# drive.net
KiCad netlist of a schematic drawn in Altium Designer
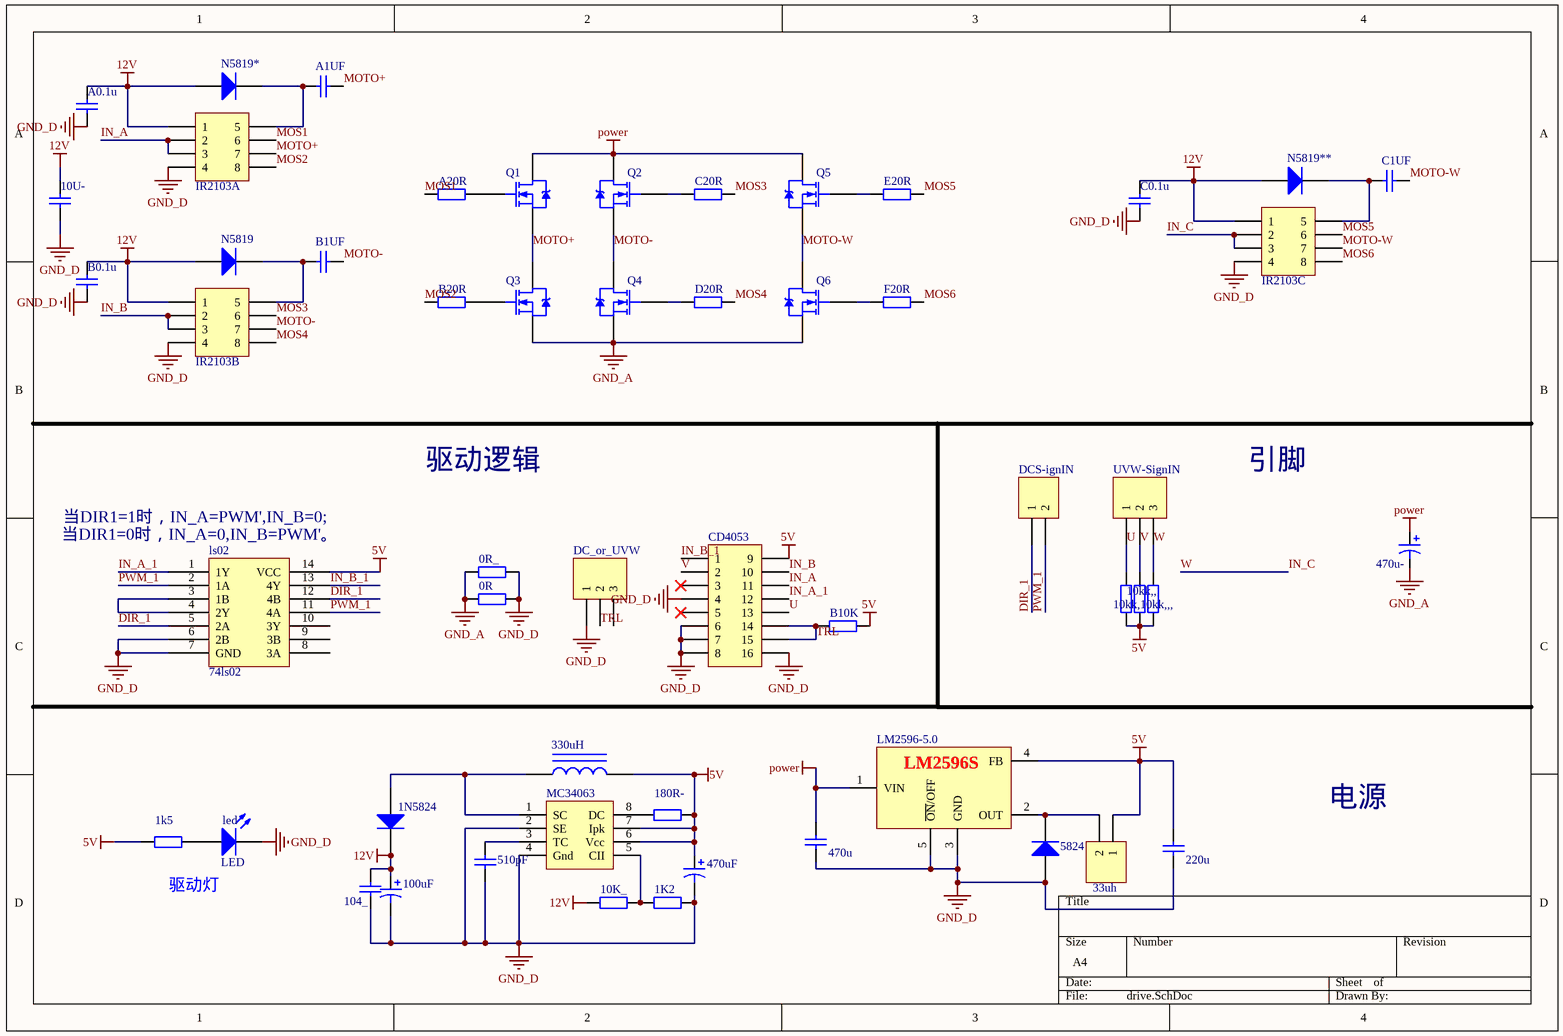
[diagram p0: drive.SchDoc]

(export (version "E")
  (design (tool "Eeschema 10.0.6"))
  (components
    (comp (ref "0R")
      (value "Res2")
      (footprint "0805")
      (description "Resistor")
      (fields (field (name "PUBLISHER") "Altium Limited"))
      (libsource (lib "") (part "Res2_1"))
    )
    (comp (ref "0R_")
      (value "Res2")
      (footprint "0805")
      (description "Resistor")
      (fields (field (name "PUBLISHER") "Altium Limited"))
      (libsource (lib "") (part "Res2_1"))
    )
    (comp (ref "1K2")
      (value "1K2")
      (footprint "0805")
      (description "Resistor")
      (fields (field (name "PUBLISHER") "Altium Limited"))
      (libsource (lib "Miscellaneous Devices") (part "Res2"))
    )
    (comp (ref "1k5") (value "1K5") (footprint "0805") (libsource (lib "主板库") (part "RES")))
    (comp (ref "1N5824")
      (value "1N5819")
      (footprint "DIODE-SMA")
      (description "1 Amp General Purpose Rectifier")
      (fields (field (name "PUBLISHER") "Altium Limited"))
      (libsource (lib "Miscellaneous Devices") (part "Diode 1N4007"))
    )
    (comp (ref "10kk,")
      (value "R4")
      (footprint "0805")
      (description "Resistor")
      (fields (field (name "PUBLISHER") "Altium Limited"))
      (libsource (lib "") (part "Res2_3"))
    )
    (comp (ref "10kk,,")
      (value "R4")
      (footprint "0805")
      (description "Resistor")
      (fields (field (name "PUBLISHER") "Altium Limited"))
      (libsource (lib "") (part "Res2_2"))
    )
    (comp (ref "10kk,,,")
      (value "R4")
      (footprint "0805")
      (description "Resistor")
      (fields (field (name "PUBLISHER") "Altium Limited"))
      (libsource (lib "") (part "Res2_2"))
    )
    (comp (ref "10K_")
      (value "10K")
      (footprint "0805")
      (description "Resistor")
      (fields (field (name "PUBLISHER") "Altium Limited"))
      (libsource (lib "Miscellaneous Devices") (part "Res2"))
    )
    (comp (ref "10U-")
      (value "0.1u2")
      (footprint "0805")
      (description "Capacitor")
      (fields (field (name "PUBLISHER") "Altium Limited"))
      (libsource (lib "Miscellaneous Devices") (part "Cap"))
    )
    (comp (ref "33uh")
      (value "Header 2")
      (footprint "HDR1X2")
      (description "Header, 2-Pin")
      (fields (field (name "PUBLISHER") "Altium Limited"))
      (libsource (lib "") (part "Header 2_1"))
    )
    (comp (ref "100uF")
      (value "100uF/25V/C")
      (footprint "capso_8*10")
      (description "Polarized Capacitor (Radial)")
      (fields (field (name "PUBLISHER") "Altium Limited"))
      (libsource (lib "Miscellaneous Devices") (part "Cap Pol1"))
    )
    (comp (ref "104_")
      (value "0.1u2")
      (footprint "0805")
      (description "Capacitor")
      (fields (field (name "PUBLISHER") "Altium Limited"))
      (libsource (lib "Miscellaneous Devices") (part "Cap"))
    )
    (comp (ref "180R-")
      (value "180R")
      (footprint "0805")
      (description "Resistor")
      (fields (field (name "PUBLISHER") "Altium Limited"))
      (libsource (lib "Miscellaneous Devices") (part "Res2"))
    )
    (comp (ref "220u")
      (value "Cap")
      (footprint "capso_8*10")
      (description "无极性电容")
      (fields (field (name "PUBLISHER") "Altium Limited"))
      (libsource (lib "Fszhang") (part "Cap"))
    )
    (comp (ref "330uH")
      (value "330uH")
      (footprint "L-SMD-12")
      (description "Magnetic-Core Inductor")
      (fields (field (name "PUBLISHER") "Altium Limited"))
      (libsource (lib "Miscellaneous Devices") (part "Inductor Iron"))
    )
    (comp (ref "470u")
      (value "Cap")
      (footprint "capso_8*10")
      (description "无极性电容")
      (fields (field (name "PUBLISHER") "Altium Limited"))
      (libsource (lib "Fszhang") (part "Cap"))
    )
    (comp (ref "470u-") (value "CAP 220") (footprint "capso_8*10") (libsource (lib "原理图封装库") (part "CAP+")))
    (comp (ref "470uF")
      (value "470uF/25V/D")
      (footprint "capso_8*10")
      (description "Polarized Capacitor (Radial)")
      (fields (field (name "PUBLISHER") "Altium Limited"))
      (libsource (lib "Miscellaneous Devices") (part "Cap Pol1"))
    )
    (comp (ref "510pF")
      (value "510pF")
      (footprint "0805")
      (description "Capacitor")
      (fields (field (name "PUBLISHER") "Altium Limited"))
      (libsource (lib "Miscellaneous Devices") (part "Cap"))
    )
    (comp (ref "5824")
      (value "Diode")
      (footprint "DIODE-SMA")
      (description "Default Diode")
      (fields (field (name "PUBLISHER") "Altium Limited"))
      (libsource (lib "Miscellaneous Devices") (part "Diode"))
    )
    (comp (ref "A0.1u")
      (value "0.1u2")
      (footprint "0805")
      (description "Capacitor")
      (fields (field (name "PUBLISHER") "Altium Limited"))
      (libsource (lib "Miscellaneous Devices") (part "Cap"))
    )
    (comp (ref "A1UF")
      (value "0.1u2")
      (footprint "0805")
      (description "Capacitor")
      (fields (field (name "PUBLISHER") "Altium Limited"))
      (libsource (lib "Miscellaneous Devices") (part "Cap"))
    )
    (comp (ref "A20R")
      (value "R1")
      (footprint "0805")
      (description "Resistor")
      (fields (field (name "PUBLISHER") "Altium Limited"))
      (libsource (lib "Miscellaneous Devices") (part "Res2"))
    )
    (comp (ref "B0.1u")
      (value "0.1u2")
      (footprint "0805")
      (description "Capacitor")
      (fields (field (name "PUBLISHER") "Altium Limited"))
      (libsource (lib "Miscellaneous Devices") (part "Cap"))
    )
    (comp (ref "B1UF")
      (value "0.1u2")
      (footprint "0805")
      (description "Capacitor")
      (fields (field (name "PUBLISHER") "Altium Limited"))
      (libsource (lib "Miscellaneous Devices") (part "Cap"))
    )
    (comp (ref "B10K")
      (value "Res2")
      (footprint "0805")
      (description "Resistor")
      (fields (field (name "PUBLISHER") "Altium Limited"))
      (libsource (lib "Miscellaneous Devices") (part "Res2"))
    )
    (comp (ref "B20R")
      (value "R3")
      (footprint "0805")
      (description "Resistor")
      (fields (field (name "PUBLISHER") "Altium Limited"))
      (libsource (lib "Miscellaneous Devices") (part "Res2"))
    )
    (comp (ref "C0.1u")
      (value "0.1u2")
      (footprint "0805")
      (description "Capacitor")
      (fields (field (name "PUBLISHER") "Altium Limited"))
      (libsource (lib "Miscellaneous Devices") (part "Cap"))
    )
    (comp (ref "C1UF")
      (value "0.1u2")
      (footprint "0805")
      (description "Capacitor")
      (fields (field (name "PUBLISHER") "Altium Limited"))
      (libsource (lib "Miscellaneous Devices") (part "Cap"))
    )
    (comp (ref "C20R")
      (value "R2")
      (footprint "0805")
      (description "Resistor")
      (fields (field (name "PUBLISHER") "Altium Limited"))
      (libsource (lib "Miscellaneous Devices") (part "Res2"))
    )
    (comp (ref "CD4053")
      (value "Header 8X2A")
      (footprint "SOP16")
      (description "Header, 8-Pin, Dual row")
      (fields (field (name "PUBLISHER") "Altium Limited"))
      (libsource (lib "Miscellaneous Connectors") (part "Header 8X2A"))
    )
    (comp (ref "D20R")
      (value "R4")
      (footprint "0805")
      (description "Resistor")
      (fields (field (name "PUBLISHER") "Altium Limited"))
      (libsource (lib "Miscellaneous Devices") (part "Res2"))
    )
    (comp (ref "DCS-ignIN")
      (value "Header 2")
      (footprint "HDR1X2")
      (description "Header, 2-Pin")
      (fields (field (name "PUBLISHER") "Altium Limited"))
      (libsource (lib "Miscellaneous Connectors") (part "Header 2"))
    )
    (comp (ref "DC_or_UVW")
      (value "MHDR1X3")
      (footprint "MHDR1X3")
      (description "Header, 3-Pin")
      (fields (field (name "PUBLISHER") "Altium Limited"))
      (libsource (lib "Miscellaneous Connectors") (part "MHDR1X3"))
    )
    (comp (ref "E20R")
      (value "R2")
      (footprint "0805")
      (description "Resistor")
      (fields (field (name "PUBLISHER") "Altium Limited"))
      (libsource (lib "Miscellaneous Devices") (part "Res2"))
    )
    (comp (ref "F20R")
      (value "R4")
      (footprint "0805")
      (description "Resistor")
      (fields (field (name "PUBLISHER") "Altium Limited"))
      (libsource (lib "Miscellaneous Devices") (part "Res2"))
    )
    (comp (ref "IR2103A")
      (value "Header 4X2A")
      (footprint "SOP8")
      (description "Header, 4-Pin, Dual row")
      (fields (field (name "PUBLISHER") "Altium Limited"))
      (libsource (lib "Miscellaneous Connectors") (part "Header 4X2A"))
    )
    (comp (ref "IR2103B")
      (value "Header 4X2A")
      (footprint "SOP8")
      (description "Header, 4-Pin, Dual row")
      (fields (field (name "PUBLISHER") "Altium Limited"))
      (libsource (lib "Miscellaneous Connectors") (part "Header 4X2A"))
    )
    (comp (ref "IR2103C")
      (value "Header 4X2A")
      (footprint "SOP8")
      (description "Header, 4-Pin, Dual row")
      (fields (field (name "PUBLISHER") "Altium Limited"))
      (libsource (lib "Miscellaneous Connectors") (part "Header 4X2A"))
    )
    (comp (ref "led") (value "LED") (footprint "LED_0805") (libsource (lib "主板库") (part "LED")))
    (comp (ref "LM2596-5.0")
      (value "LM2596S")
      (footprint "TO-263-5")
      (description "NS SIMPLE SWITCHER?Power Converter 150 kHz")
      (libsource (lib "电源管理") (part "LM2596S"))
    )
    (comp (ref "ls02")
      (value "74ls02")
      (footprint "SO-14")
      (libsource (lib "Integrated_Library_errowily") (part "74ls02"))
    )
    (comp (ref "MC34063")
      (value "MC34063")
      (footprint "SOP8")
      (libsource (lib "MC34063") (part "Component_1"))
    )
    (comp (ref "N5819")
      (value "1N5819")
      (footprint "V3封装库:D1206")
      (description "1 Amp Fast Recovery Rectifier")
      (fields (field (name "PUBLISHER") "Altium Limited"))
      (libsource (lib "Miscellaneous Devices") (part "Diode 1N4934"))
    )
    (comp (ref "N5819*")
      (value "1N5819")
      (footprint "V3封装库:D1206")
      (description "1 Amp Fast Recovery Rectifier")
      (fields (field (name "PUBLISHER") "Altium Limited"))
      (libsource (lib "Miscellaneous Devices") (part "Diode 1N4934"))
    )
    (comp (ref "N5819**")
      (value "1N5819")
      (footprint "V3封装库:D1206")
      (description "1 Amp Fast Recovery Rectifier")
      (fields (field (name "PUBLISHER") "Altium Limited"))
      (libsource (lib "Miscellaneous Devices") (part "Diode 1N4934"))
    )
    (comp (ref "Q1")
      (value "LR7843")
      (footprint "我的封装库:TO-263")
      (description "N-Channel Power MOSFET")
      (fields (field (name "PUBLISHER") "Altium Limited"))
      (libsource (lib "Miscellaneous Devices") (part "NMOS-2"))
    )
    (comp (ref "Q2")
      (value "LR7843")
      (footprint "我的封装库:TO-263")
      (description "N-Channel Power MOSFET")
      (fields (field (name "PUBLISHER") "Altium Limited"))
      (libsource (lib "Miscellaneous Devices") (part "NMOS-2"))
    )
    (comp (ref "Q3")
      (value "LR7843")
      (footprint "我的封装库:TO-263")
      (description "N-Channel Power MOSFET")
      (fields (field (name "PUBLISHER") "Altium Limited"))
      (libsource (lib "Miscellaneous Devices") (part "NMOS-2"))
    )
    (comp (ref "Q4")
      (value "LR7843")
      (footprint "我的封装库:TO-263")
      (description "N-Channel Power MOSFET")
      (fields (field (name "PUBLISHER") "Altium Limited"))
      (libsource (lib "Miscellaneous Devices") (part "NMOS-2"))
    )
    (comp (ref "Q5")
      (value "LR7843")
      (footprint "我的封装库:TO-263")
      (description "N-Channel Power MOSFET")
      (fields (field (name "PUBLISHER") "Altium Limited"))
      (libsource (lib "Miscellaneous Devices") (part "NMOS-2"))
    )
    (comp (ref "Q6")
      (value "LR7843")
      (footprint "我的封装库:TO-263")
      (description "N-Channel Power MOSFET")
      (fields (field (name "PUBLISHER") "Altium Limited"))
      (libsource (lib "Miscellaneous Devices") (part "NMOS-2"))
    )
    (comp (ref "UVW-SignIN")
      (value "Header 3")
      (footprint "HDR1X3")
      (description "Header, 3-Pin")
      (fields (field (name "PUBLISHER") "Altium Limited"))
      (libsource (lib "Miscellaneous Connectors") (part "Header 3"))
    )
  )
  (nets
    (net (code "1") (name "/DIR_1") (class "Default")
      (node (ref "DCS-ignIN") (pin "1") (pinfunction "1_1") (pintype "passive"))
      (node (ref "ls02") (pin "12") (pinfunction "4B_12") (pintype "passive"))
      (node (ref "ls02") (pin "5") (pinfunction "2A_5") (pintype "passive"))
    )
    (net (code "2") (name "/IN_A") (class "Default")
      (node (ref "CD4053") (pin "11") (pinfunction "11_11") (pintype "passive"))
      (node (ref "IR2103A") (pin "2") (pinfunction "2_2") (pintype "passive"))
      (node (ref "IR2103A") (pin "3") (pinfunction "3_3") (pintype "passive"))
    )
    (net (code "3") (name "/IN_A_1") (class "Default")
      (node (ref "CD4053") (pin "12") (pinfunction "12_12") (pintype "passive"))
      (node (ref "ls02") (pin "1") (pinfunction "1Y_1") (pintype "passive"))
    )
    (net (code "4") (name "/IN_B") (class "Default")
      (node (ref "CD4053") (pin "10") (pinfunction "10_10") (pintype "passive"))
      (node (ref "IR2103B") (pin "2") (pinfunction "2_2") (pintype "passive"))
      (node (ref "IR2103B") (pin "3") (pinfunction "3_3") (pintype "passive"))
    )
    (net (code "5") (name "/IN_B_1") (class "Default")
      (node (ref "CD4053") (pin "1") (pinfunction "1_1") (pintype "passive"))
      (node (ref "ls02") (pin "13") (pinfunction "4Y_13") (pintype "passive"))
    )
    (net (code "6") (name "/IN_C") (class "Default")
      (node (ref "10kk,,,") (pin "2") (pinfunction "2_2") (pintype "passive"))
      (node (ref "IR2103C") (pin "2") (pinfunction "2_2") (pintype "passive"))
      (node (ref "IR2103C") (pin "3") (pinfunction "3_3") (pintype "passive"))
      (node (ref "UVW-SignIN") (pin "3") (pinfunction "3_3") (pintype "passive"))
    )
    (net (code "7") (name "/MOS1") (class "Default")
      (node (ref "A20R") (pin "1") (pinfunction "1_1") (pintype "passive"))
      (node (ref "IR2103A") (pin "6") (pinfunction "6_6") (pintype "passive"))
    )
    (net (code "8") (name "/MOS2") (class "Default")
      (node (ref "B20R") (pin "1") (pinfunction "1_1") (pintype "passive"))
      (node (ref "IR2103A") (pin "8") (pinfunction "8_8") (pintype "passive"))
    )
    (net (code "9") (name "/MOS3") (class "Default")
      (node (ref "C20R") (pin "2") (pinfunction "2_2") (pintype "passive"))
      (node (ref "IR2103B") (pin "6") (pinfunction "6_6") (pintype "passive"))
    )
    (net (code "10") (name "/MOS4") (class "Default")
      (node (ref "D20R") (pin "2") (pinfunction "2_2") (pintype "passive"))
      (node (ref "IR2103B") (pin "8") (pinfunction "8_8") (pintype "passive"))
    )
    (net (code "11") (name "/MOS5") (class "Default")
      (node (ref "E20R") (pin "2") (pinfunction "2_2") (pintype "passive"))
      (node (ref "IR2103C") (pin "6") (pinfunction "6_6") (pintype "passive"))
    )
    (net (code "12") (name "/MOS6") (class "Default")
      (node (ref "F20R") (pin "2") (pinfunction "2_2") (pintype "passive"))
      (node (ref "IR2103C") (pin "8") (pinfunction "8_8") (pintype "passive"))
    )
    (net (code "13") (name "/MOTO+") (class "Default")
      (node (ref "A1UF") (pin "1") (pinfunction "1_1") (pintype "passive"))
      (node (ref "IR2103A") (pin "7") (pinfunction "7_7") (pintype "passive"))
      (node (ref "Q1") (pin "3") (pinfunction "S_3") (pintype "passive"))
      (node (ref "Q3") (pin "2") (pinfunction "D_2") (pintype "passive"))
    )
    (net (code "14") (name "/MOTO-") (class "Default")
      (node (ref "B1UF") (pin "1") (pinfunction "1_1") (pintype "passive"))
      (node (ref "IR2103B") (pin "7") (pinfunction "7_7") (pintype "passive"))
      (node (ref "Q2") (pin "3") (pinfunction "S_3") (pintype "passive"))
      (node (ref "Q4") (pin "2") (pinfunction "D_2") (pintype "passive"))
    )
    (net (code "15") (name "/MOTO-W") (class "Default")
      (node (ref "C1UF") (pin "1") (pinfunction "1_1") (pintype "passive"))
      (node (ref "IR2103C") (pin "7") (pinfunction "7_7") (pintype "passive"))
      (node (ref "Q5") (pin "3") (pinfunction "S_3") (pintype "passive"))
      (node (ref "Q6") (pin "2") (pinfunction "D_2") (pintype "passive"))
    )
    (net (code "16") (name "/PWM_1") (class "Default")
      (node (ref "DCS-ignIN") (pin "2") (pinfunction "2_2") (pintype "passive"))
      (node (ref "ls02") (pin "11") (pinfunction "4A_11") (pintype "passive"))
      (node (ref "ls02") (pin "2") (pinfunction "1A_2") (pintype "passive"))
    )
    (net (code "17") (name "/TRL") (class "Default")
      (node (ref "B10K") (pin "1") (pinfunction "1_1") (pintype "passive"))
      (node (ref "CD4053") (pin "14") (pinfunction "14_14") (pintype "passive"))
      (node (ref "CD4053") (pin "15") (pinfunction "15_15") (pintype "passive"))
      (node (ref "DC_or_UVW") (pin "2") (pinfunction "2_2") (pintype "passive"))
    )
    (net (code "18") (name "/U") (class "Default")
      (node (ref "10kk,") (pin "1") (pinfunction "1_1") (pintype "passive"))
      (node (ref "CD4053") (pin "13") (pinfunction "13_13") (pintype "passive"))
      (node (ref "UVW-SignIN") (pin "1") (pinfunction "1_1") (pintype "passive"))
    )
    (net (code "19") (name "/V") (class "Default")
      (node (ref "10kk,,") (pin "2") (pinfunction "2_2") (pintype "passive"))
      (node (ref "CD4053") (pin "2") (pinfunction "2_2") (pintype "passive"))
      (node (ref "UVW-SignIN") (pin "2") (pinfunction "2_2") (pintype "passive"))
    )
    (net (code "20") (name "5V") (class "Default")
      (node (ref "10kk,") (pin "2") (pinfunction "2_2") (pintype "passive"))
      (node (ref "10kk,,") (pin "1") (pinfunction "1_1") (pintype "passive"))
      (node (ref "10kk,,,") (pin "1") (pinfunction "1_1") (pintype "passive"))
      (node (ref "180R-") (pin "2") (pinfunction "2_2") (pintype "passive"))
      (node (ref "1k5") (pin "1") (pinfunction "1_1") (pintype "passive"))
      (node (ref "220u") (pin "1") (pinfunction "1_1") (pintype "passive"))
      (node (ref "330uH") (pin "2") (pinfunction "2_2") (pintype "passive"))
      (node (ref "33uh") (pin "1") (pinfunction "1_1") (pintype "passive"))
      (node (ref "470uF") (pin "1") (pinfunction "1_1") (pintype "passive"))
      (node (ref "B10K") (pin "2") (pinfunction "2_2") (pintype "passive"))
      (node (ref "CD4053") (pin "9") (pinfunction "9_9") (pintype "passive"))
      (node (ref "LM2596-5.0") (pin "4") (pinfunction "FB_4") (pintype "passive"))
      (node (ref "MC34063") (pin "6") (pinfunction "Vcc_6") (pintype "passive"))
      (node (ref "MC34063") (pin "7") (pinfunction "Ipk_7") (pintype "passive"))
      (node (ref "ls02") (pin "14") (pinfunction "VCC_14") (pintype "passive"))
    )
    (net (code "21") (name "12V") (class "Default")
      (node (ref "100uF") (pin "1") (pinfunction "1_1") (pintype "passive"))
      (node (ref "104_") (pin "1") (pinfunction "1_1") (pintype "passive"))
      (node (ref "10K_") (pin "1") (pinfunction "1_1") (pintype "passive"))
      (node (ref "10U-") (pin "1") (pinfunction "1_1") (pintype "passive"))
      (node (ref "1N5824") (pin "2") (pinfunction "K_2") (pintype "passive"))
      (node (ref "A0.1u") (pin "1") (pinfunction "1_1") (pintype "passive"))
      (node (ref "B0.1u") (pin "1") (pinfunction "1_1") (pintype "passive"))
      (node (ref "C0.1u") (pin "1") (pinfunction "1_1") (pintype "passive"))
      (node (ref "IR2103A") (pin "1") (pinfunction "1_1") (pintype "passive"))
      (node (ref "IR2103B") (pin "1") (pinfunction "1_1") (pintype "passive"))
      (node (ref "IR2103C") (pin "1") (pinfunction "1_1") (pintype "passive"))
      (node (ref "N5819") (pin "1") (pinfunction "A_1") (pintype "passive"))
      (node (ref "N5819*") (pin "1") (pinfunction "A_1") (pintype "passive"))
      (node (ref "N5819**") (pin "1") (pinfunction "A_1") (pintype "passive"))
    )
    (net (code "22") (name "GND_A") (class "Default")
      (node (ref "0R") (pin "2") (pinfunction "2_2") (pintype "passive"))
      (node (ref "0R_") (pin "2") (pinfunction "2_2") (pintype "passive"))
      (node (ref "470u-") (pin "2") (pinfunction "2_2") (pintype "passive"))
      (node (ref "Q3") (pin "3") (pinfunction "S_3") (pintype "passive"))
      (node (ref "Q4") (pin "3") (pinfunction "S_3") (pintype "passive"))
      (node (ref "Q6") (pin "3") (pinfunction "S_3") (pintype "passive"))
    )
    (net (code "23") (name "GND_D") (class "Default")
      (node (ref "0R") (pin "1") (pinfunction "1_1") (pintype "passive"))
      (node (ref "0R_") (pin "1") (pinfunction "1_1") (pintype "passive"))
      (node (ref "100uF") (pin "2") (pinfunction "2_2") (pintype "passive"))
      (node (ref "104_") (pin "2") (pinfunction "2_2") (pintype "passive"))
      (node (ref "10U-") (pin "2") (pinfunction "2_2") (pintype "passive"))
      (node (ref "1K2") (pin "2") (pinfunction "2_2") (pintype "passive"))
      (node (ref "220u") (pin "2") (pinfunction "2_2") (pintype "passive"))
      (node (ref "470u") (pin "2") (pinfunction "2_2") (pintype "passive"))
      (node (ref "470uF") (pin "2") (pinfunction "2_2") (pintype "passive"))
      (node (ref "510pF") (pin "1") (pinfunction "1_1") (pintype "passive"))
      (node (ref "5824") (pin "1") (pinfunction "A_1") (pintype "passive"))
      (node (ref "A0.1u") (pin "2") (pinfunction "2_2") (pintype "passive"))
      (node (ref "B0.1u") (pin "2") (pinfunction "2_2") (pintype "passive"))
      (node (ref "C0.1u") (pin "2") (pinfunction "2_2") (pintype "passive"))
      (node (ref "CD4053") (pin "16") (pinfunction "16_16") (pintype "passive"))
      (node (ref "CD4053") (pin "4") (pinfunction "4_4") (pintype "passive"))
      (node (ref "CD4053") (pin "6") (pinfunction "6_6") (pintype "passive"))
      (node (ref "CD4053") (pin "7") (pinfunction "7_7") (pintype "passive"))
      (node (ref "CD4053") (pin "8") (pinfunction "8_8") (pintype "passive"))
      (node (ref "DC_or_UVW") (pin "1") (pinfunction "1_1") (pintype "passive"))
      (node (ref "IR2103A") (pin "4") (pinfunction "4_4") (pintype "passive"))
      (node (ref "IR2103B") (pin "4") (pinfunction "4_4") (pintype "passive"))
      (node (ref "IR2103C") (pin "4") (pinfunction "4_4") (pintype "passive"))
      (node (ref "LM2596-5.0") (pin "3") (pinfunction "GND_3") (pintype "passive"))
      (node (ref "LM2596-5.0") (pin "5") (pinfunction "~{ON}/OFF_5") (pintype "passive"))
      (node (ref "MC34063") (pin "2") (pinfunction "SE_2") (pintype "passive"))
      (node (ref "MC34063") (pin "4") (pinfunction "Gnd_4") (pintype "passive"))
      (node (ref "led") (pin "2") (pinfunction "K_2") (pintype "passive"))
      (node (ref "ls02") (pin "6") (pinfunction "2B_6") (pintype "passive"))
      (node (ref "ls02") (pin "7") (pinfunction "GND_7") (pintype "passive"))
    )
    (net (code "24") (name "Net-(1N5824-A)") (class "Default")
      (node (ref "1N5824") (pin "1") (pinfunction "A_1") (pintype "passive"))
      (node (ref "330uH") (pin "1") (pinfunction "1_1") (pintype "passive"))
      (node (ref "MC34063") (pin "1") (pinfunction "SC_1") (pintype "passive"))
    )
    (net (code "25") (name "Net-(5824-K)") (class "Default")
      (node (ref "33uh") (pin "2") (pinfunction "2_2") (pintype "passive"))
      (node (ref "5824") (pin "2") (pinfunction "K_2") (pintype "passive"))
      (node (ref "LM2596-5.0") (pin "2") (pinfunction "OUT_2") (pintype "passive"))
    )
    (net (code "26") (name "Net-(MC34063-CII)") (class "Default")
      (node (ref "10K_") (pin "2") (pinfunction "2_2") (pintype "passive"))
      (node (ref "1K2") (pin "1") (pinfunction "1_1") (pintype "passive"))
      (node (ref "MC34063") (pin "5") (pinfunction "CII_5") (pintype "passive"))
    )
    (net (code "27") (name "Net-(MC34063-DC)") (class "Default")
      (node (ref "180R-") (pin "1") (pinfunction "1_1") (pintype "passive"))
      (node (ref "MC34063") (pin "8") (pinfunction "DC_8") (pintype "passive"))
    )
    (net (code "28") (name "Net-(MC34063-TC)") (class "Default")
      (node (ref "510pF") (pin "2") (pinfunction "2_2") (pintype "passive"))
      (node (ref "MC34063") (pin "3") (pinfunction "TC_3") (pintype "passive"))
    )
    (net (code "29") (name "Net-(N5819**-K)") (class "Default")
      (node (ref "C1UF") (pin "2") (pinfunction "2_2") (pintype "passive"))
      (node (ref "IR2103C") (pin "5") (pinfunction "5_5") (pintype "passive"))
      (node (ref "N5819**") (pin "2") (pinfunction "K_2") (pintype "passive"))
    )
    (net (code "30") (name "Net-(N5819*-K)") (class "Default")
      (node (ref "A1UF") (pin "2") (pinfunction "2_2") (pintype "passive"))
      (node (ref "IR2103A") (pin "5") (pinfunction "5_5") (pintype "passive"))
      (node (ref "N5819*") (pin "2") (pinfunction "K_2") (pintype "passive"))
    )
    (net (code "31") (name "Net-(N5819-K)") (class "Default")
      (node (ref "B1UF") (pin "2") (pinfunction "2_2") (pintype "passive"))
      (node (ref "IR2103B") (pin "5") (pinfunction "5_5") (pintype "passive"))
      (node (ref "N5819") (pin "2") (pinfunction "K_2") (pintype "passive"))
    )
    (net (code "32") (name "Net-(Q1-G)") (class "Default")
      (node (ref "A20R") (pin "2") (pinfunction "2_2") (pintype "passive"))
      (node (ref "Q1") (pin "1") (pinfunction "G_1") (pintype "passive"))
    )
    (net (code "33") (name "Net-(Q2-G)") (class "Default")
      (node (ref "C20R") (pin "1") (pinfunction "1_1") (pintype "passive"))
      (node (ref "Q2") (pin "1") (pinfunction "G_1") (pintype "passive"))
    )
    (net (code "34") (name "Net-(Q3-G)") (class "Default")
      (node (ref "B20R") (pin "2") (pinfunction "2_2") (pintype "passive"))
      (node (ref "Q3") (pin "1") (pinfunction "G_1") (pintype "passive"))
    )
    (net (code "35") (name "Net-(Q4-G)") (class "Default")
      (node (ref "D20R") (pin "1") (pinfunction "1_1") (pintype "passive"))
      (node (ref "Q4") (pin "1") (pinfunction "G_1") (pintype "passive"))
    )
    (net (code "36") (name "Net-(Q5-G)") (class "Default")
      (node (ref "E20R") (pin "1") (pinfunction "1_1") (pintype "passive"))
      (node (ref "Q5") (pin "1") (pinfunction "G_1") (pintype "passive"))
    )
    (net (code "37") (name "Net-(Q6-G)") (class "Default")
      (node (ref "F20R") (pin "1") (pinfunction "1_1") (pintype "passive"))
      (node (ref "Q6") (pin "1") (pinfunction "G_1") (pintype "passive"))
    )
    (net (code "38") (name "Net-(led-A)") (class "Default")
      (node (ref "1k5") (pin "2") (pinfunction "2_2") (pintype "passive"))
      (node (ref "led") (pin "1") (pinfunction "A_1") (pintype "passive"))
    )
    (net (code "39") (name "Net-(ls02-1B)") (class "Default")
      (node (ref "ls02") (pin "3") (pinfunction "1B_3") (pintype "passive"))
      (node (ref "ls02") (pin "4") (pinfunction "2Y_4") (pintype "passive"))
    )
    (net (code "40") (name "power") (class "Default")
      (node (ref "470u") (pin "1") (pinfunction "1_1") (pintype "passive"))
      (node (ref "470u-") (pin "1") (pinfunction "1_1") (pintype "passive"))
      (node (ref "LM2596-5.0") (pin "1") (pinfunction "VIN_1") (pintype "passive"))
      (node (ref "Q1") (pin "2") (pinfunction "D_2") (pintype "passive"))
      (node (ref "Q2") (pin "2") (pinfunction "D_2") (pintype "passive"))
      (node (ref "Q5") (pin "2") (pinfunction "D_2") (pintype "passive"))
    )
    (net (code "41") (name "unconnected-(CD4053-Pad3)") (class "Default")
      (node (ref "CD4053") (pin "3") (pinfunction "3_3") (pintype "passive+no_connect"))
    )
    (net (code "42") (name "unconnected-(CD4053-Pad5)") (class "Default")
      (node (ref "CD4053") (pin "5") (pinfunction "5_5") (pintype "passive+no_connect"))
    )
    (net (code "43") (name "unconnected-(DC_or_UVW-Pad3)") (class "Default")
      (node (ref "DC_or_UVW") (pin "3") (pinfunction "3_3") (pintype "passive"))
    )
    (net (code "44") (name "unconnected-(ls02-3A-Pad8)") (class "Default")
      (node (ref "ls02") (pin "8") (pinfunction "3A_8") (pintype "passive"))
    )
    (net (code "45") (name "unconnected-(ls02-3B-Pad9)") (class "Default")
      (node (ref "ls02") (pin "9") (pinfunction "3B_9") (pintype "passive"))
    )
    (net (code "46") (name "unconnected-(ls02-3Y-Pad10)") (class "Default")
      (node (ref "ls02") (pin "10") (pinfunction "3Y_10") (pintype "passive"))
    )
  )
)
